# Schematic-1.net
KiCad netlist of a schematic drawn in EAGLE
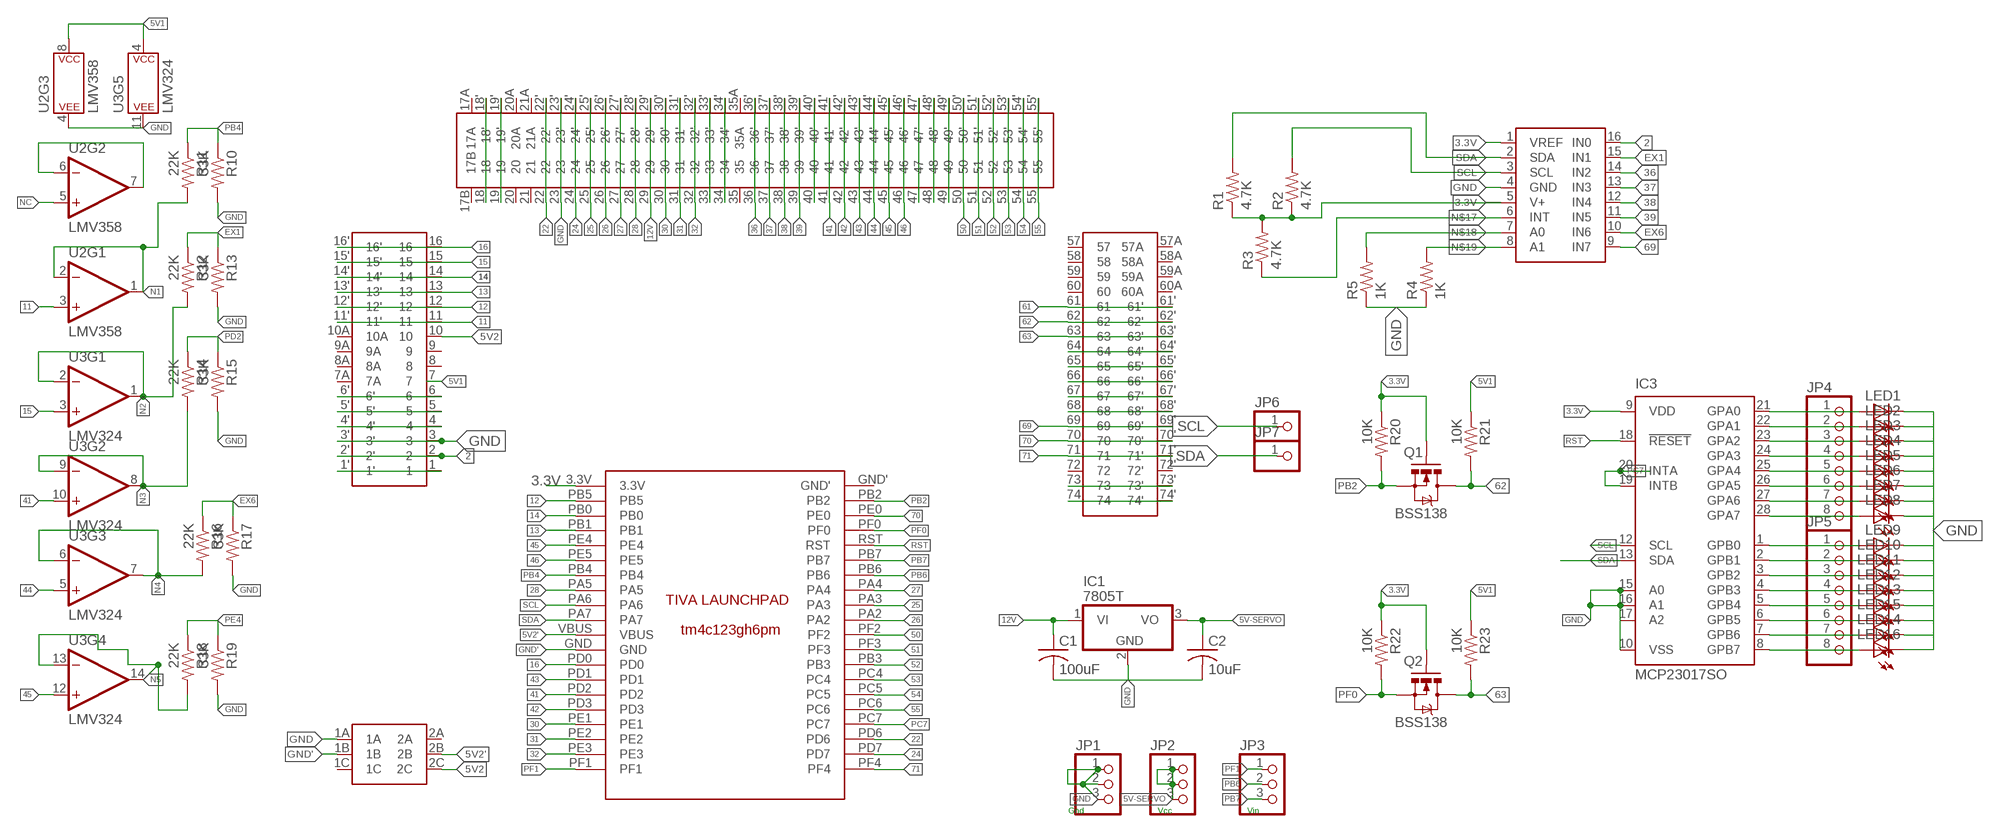
[diagram p0: schematic, sheet 1]

(export (version "E")
  (design (tool "Eeschema 10.0.6"))
  (components
    (comp (ref "C1")
      (value "100uF")
      (footprint "eagle-import:C025-030X050")
      (libsource (lib "eagle-import") (part "C-US025-030X050"))
    )
    (comp (ref "C2")
      (value "10uF")
      (footprint "eagle-import:C025-030X050")
      (libsource (lib "eagle-import") (part "C-US025-030X050"))
    )
    (comp (ref "IC1")
      (value "7805T")
      (footprint "eagle-import:TO220H")
      (libsource (lib "eagle-import") (part "78T05"))
    )
    (comp (ref "IC3")
      (value "MCP23017SO")
      (footprint "eagle-import:SO28W")
      (libsource (lib "eagle-import") (part "MCP23017SO"))
    )
    (comp (ref "JP1")
      (value "PINHD-1X3")
      (footprint "eagle-import:1X03")
      (libsource (lib "eagle-import") (part "PINHD-1X3"))
    )
    (comp (ref "JP2")
      (value "PINHD-1X3")
      (footprint "eagle-import:1X03")
      (libsource (lib "eagle-import") (part "PINHD-1X3"))
    )
    (comp (ref "JP3")
      (value "PINHD-1X3")
      (footprint "eagle-import:1X03")
      (libsource (lib "eagle-import") (part "PINHD-1X3"))
    )
    (comp (ref "JP4")
      (value "PINHD-1X8BIG")
      (footprint "eagle-import:1X08-BIG")
      (libsource (lib "eagle-import") (part "PINHD-1X8BIG"))
    )
    (comp (ref "JP5")
      (value "PINHD-1X8BIG")
      (footprint "eagle-import:1X08-BIG")
      (libsource (lib "eagle-import") (part "PINHD-1X8BIG"))
    )
    (comp (ref "JP6")
      (value "PINHD-1X1")
      (footprint "eagle-import:1X01")
      (libsource (lib "eagle-import") (part "PINHD-1X1"))
    )
    (comp (ref "JP7")
      (value "PINHD-1X1")
      (footprint "eagle-import:1X01")
      (libsource (lib "eagle-import") (part "PINHD-1X1"))
    )
    (comp (ref "LED1")
      (value "LEDSMT1206")
      (footprint "eagle-import:1206")
      (libsource (lib "eagle-import") (part "LEDSMT1206"))
    )
    (comp (ref "LED2")
      (value "LEDSMT1206")
      (footprint "eagle-import:1206")
      (libsource (lib "eagle-import") (part "LEDSMT1206"))
    )
    (comp (ref "LED3")
      (value "LEDSMT1206")
      (footprint "eagle-import:1206")
      (libsource (lib "eagle-import") (part "LEDSMT1206"))
    )
    (comp (ref "LED4")
      (value "LEDSMT1206")
      (footprint "eagle-import:1206")
      (libsource (lib "eagle-import") (part "LEDSMT1206"))
    )
    (comp (ref "LED5")
      (value "LEDSMT1206")
      (footprint "eagle-import:1206")
      (libsource (lib "eagle-import") (part "LEDSMT1206"))
    )
    (comp (ref "LED6")
      (value "LEDSMT1206")
      (footprint "eagle-import:1206")
      (libsource (lib "eagle-import") (part "LEDSMT1206"))
    )
    (comp (ref "LED7")
      (value "LEDSMT1206")
      (footprint "eagle-import:1206")
      (libsource (lib "eagle-import") (part "LEDSMT1206"))
    )
    (comp (ref "LED8")
      (value "LEDSMT1206")
      (footprint "eagle-import:1206")
      (libsource (lib "eagle-import") (part "LEDSMT1206"))
    )
    (comp (ref "LED9")
      (value "LEDSMT1206")
      (footprint "eagle-import:1206")
      (libsource (lib "eagle-import") (part "LEDSMT1206"))
    )
    (comp (ref "LED10")
      (value "LEDSMT1206")
      (footprint "eagle-import:1206")
      (libsource (lib "eagle-import") (part "LEDSMT1206"))
    )
    (comp (ref "LED11")
      (value "LEDSMT1206")
      (footprint "eagle-import:1206")
      (libsource (lib "eagle-import") (part "LEDSMT1206"))
    )
    (comp (ref "LED12")
      (value "LEDSMT1206")
      (footprint "eagle-import:1206")
      (libsource (lib "eagle-import") (part "LEDSMT1206"))
    )
    (comp (ref "LED13")
      (value "LEDSMT1206")
      (footprint "eagle-import:1206")
      (libsource (lib "eagle-import") (part "LEDSMT1206"))
    )
    (comp (ref "LED14")
      (value "LEDSMT1206")
      (footprint "eagle-import:1206")
      (libsource (lib "eagle-import") (part "LEDSMT1206"))
    )
    (comp (ref "LED15")
      (value "LEDSMT1206")
      (footprint "eagle-import:1206")
      (libsource (lib "eagle-import") (part "LEDSMT1206"))
    )
    (comp (ref "LED16")
      (value "LEDSMT1206")
      (footprint "eagle-import:1206")
      (libsource (lib "eagle-import") (part "LEDSMT1206"))
    )
    (comp (ref "Q1")
      (value "BSS138")
      (footprint "eagle-import:SOT23-3")
      (libsource (lib "eagle-import") (part "MOSFET-NCHANNELSMD"))
    )
    (comp (ref "Q2")
      (value "BSS138")
      (footprint "eagle-import:SOT23-3")
      (libsource (lib "eagle-import") (part "MOSFET-NCHANNELSMD"))
    )
    (comp (ref "R1")
      (value "4.7K")
      (footprint "eagle-import:M1206")
      (libsource (lib "eagle-import") (part "rcl_R-US_M1206"))
    )
    (comp (ref "R2")
      (value "4.7K")
      (footprint "eagle-import:M1206")
      (libsource (lib "eagle-import") (part "rcl_R-US_M1206"))
    )
    (comp (ref "R3")
      (value "4.7K")
      (footprint "eagle-import:M1206")
      (libsource (lib "eagle-import") (part "rcl_R-US_M1206"))
    )
    (comp (ref "R4")
      (value "1K")
      (footprint "eagle-import:M1206")
      (libsource (lib "eagle-import") (part "rcl_R-US_M1206"))
    )
    (comp (ref "R5")
      (value "1K")
      (footprint "eagle-import:M1206")
      (libsource (lib "eagle-import") (part "rcl_R-US_M1206"))
    )
    (comp (ref "R10")
      (value "33K")
      (footprint "eagle-import:M1206")
      (libsource (lib "eagle-import") (part "R-US_M1206"))
    )
    (comp (ref "R11")
      (value "22K")
      (footprint "eagle-import:M1206")
      (libsource (lib "eagle-import") (part "R-US_M1206"))
    )
    (comp (ref "R12")
      (value "22K")
      (footprint "eagle-import:M1206")
      (libsource (lib "eagle-import") (part "R-US_M1206"))
    )
    (comp (ref "R13")
      (value "33K")
      (footprint "eagle-import:M1206")
      (libsource (lib "eagle-import") (part "R-US_M1206"))
    )
    (comp (ref "R14")
      (value "22K")
      (footprint "eagle-import:M1206")
      (libsource (lib "eagle-import") (part "R-US_M1206"))
    )
    (comp (ref "R15")
      (value "33K")
      (footprint "eagle-import:M1206")
      (libsource (lib "eagle-import") (part "R-US_M1206"))
    )
    (comp (ref "R16")
      (value "22K")
      (footprint "eagle-import:M1206")
      (libsource (lib "eagle-import") (part "R-US_M1206"))
    )
    (comp (ref "R17")
      (value "33K")
      (footprint "eagle-import:M1206")
      (libsource (lib "eagle-import") (part "R-US_M1206"))
    )
    (comp (ref "R18")
      (value "22K")
      (footprint "eagle-import:M1206")
      (libsource (lib "eagle-import") (part "R-US_M1206"))
    )
    (comp (ref "R19")
      (value "33K")
      (footprint "eagle-import:M1206")
      (libsource (lib "eagle-import") (part "R-US_M1206"))
    )
    (comp (ref "R20")
      (value "10K")
      (footprint "eagle-import:1206")
      (libsource (lib "eagle-import") (part "RESISTOR1206"))
    )
    (comp (ref "R21")
      (value "10K")
      (footprint "eagle-import:1206")
      (libsource (lib "eagle-import") (part "RESISTOR1206"))
    )
    (comp (ref "R22")
      (value "10K")
      (footprint "eagle-import:1206")
      (libsource (lib "eagle-import") (part "RESISTOR1206"))
    )
    (comp (ref "R23")
      (value "10K")
      (footprint "eagle-import:1206")
      (libsource (lib "eagle-import") (part "RESISTOR1206"))
    )
    (comp (ref "U$1")
      (value "DAUGHTERBOARDDAUGHTERBOARD")
      (footprint "eagle-import:DAUGHTERBOARD")
      (libsource (lib "eagle-import") (part "DAUGHTERBOARDDAUGHTERBOARD"))
    )
    (comp (ref "U$2")
      (value "TIVA_LAUNCHPADTIVA_LAUNCHPAD")
      (footprint "eagle-import:TIVA_LAUNCHPAD")
      (libsource (lib "eagle-import") (part "TIVA_LAUNCHPADTIVA_LAUNCHPAD"))
    )
    (comp (ref "U$3")
      (value "SELF-LOCKING_SWITCHSELF-LOCKING_SWITCH")
      (footprint "eagle-import:SELF-LOCKING_SWITCH")
      (libsource (lib "eagle-import") (part "SELF-LOCKING_SWITCHSELF-LOCKING_SWITCH"))
    )
    (comp (ref "U$4")
      (value "ADC128D818")
      (footprint "eagle-import:ADC12_SD")
      (libsource (lib "eagle-import") (part "ADC128D818"))
    )
    (comp (ref "U2")
      (value "LMV358")
      (footprint "eagle-import:SO08")
      (libsource (lib "eagle-import") (part "LMV358SOIC"))
    )
    (comp (ref "U3")
      (value "LMV324")
      (footprint "eagle-import:SO14")
      (libsource (lib "eagle-import") (part "LMV324"))
    )
  )
  (nets
    (net (code "1") (name "2") (class "Default")
      (node (ref "U$1") (pin "2") (pinfunction "2_2") (pintype "output"))
      (node (ref "U$1") (pin "2'") (pinfunction "2'_2'") (pintype "output"))
      (node (ref "U$4") (pin "16") (pinfunction "IN0_16") (pintype "bidirectional"))
    )
    (net (code "2") (name "3.3V") (class "Default")
      (node (ref "IC3") (pin "9") (pinfunction "VDD_9") (pintype "power_in"))
      (node (ref "Q1") (pin "1") (pinfunction "G_1") (pintype "passive"))
      (node (ref "Q2") (pin "1") (pinfunction "G_1") (pintype "passive"))
      (node (ref "R1") (pin "1") (pinfunction "1_1") (pintype "passive"))
      (node (ref "R2") (pin "1") (pinfunction "1_1") (pintype "passive"))
      (node (ref "R20") (pin "1") (pinfunction "1_1") (pintype "passive"))
      (node (ref "R22") (pin "1") (pinfunction "1_1") (pintype "passive"))
      (node (ref "R3") (pin "2") (pinfunction "2_2") (pintype "passive"))
      (node (ref "U$2") (pin "3.3V") (pinfunction "3.3V_3.3V") (pintype "bidirectional"))
      (node (ref "U$4") (pin "1") (pinfunction "VREF_1") (pintype "bidirectional"))
      (node (ref "U$4") (pin "5") (pinfunction "V+_5") (pintype "bidirectional"))
    )
    (net (code "3") (name "5V-SERVO") (class "Default")
      (node (ref "C2") (pin "1") (pinfunction "1_1") (pintype "passive"))
      (node (ref "IC1") (pin "3") (pinfunction "VO_3") (pintype "passive"))
      (node (ref "JP2") (pin "1") (pinfunction "1_1") (pintype "passive"))
      (node (ref "JP2") (pin "2") (pinfunction "2_2") (pintype "passive"))
      (node (ref "JP2") (pin "3") (pinfunction "3_3") (pintype "passive"))
    )
    (net (code "4") (name "5V1") (class "Default")
      (node (ref "R21") (pin "1") (pinfunction "1_1") (pintype "passive"))
      (node (ref "R23") (pin "1") (pinfunction "1_1") (pintype "passive"))
      (node (ref "U$1") (pin "7") (pinfunction "7_7") (pintype "output"))
      (node (ref "U2") (pin "8") (pinfunction "P$V+_8") (pintype "bidirectional"))
      (node (ref "U3") (pin "4") (pinfunction "P$V+_4") (pintype "bidirectional"))
    )
    (net (code "5") (name "5V2") (class "Default")
      (node (ref "U$1") (pin "10") (pinfunction "10_10") (pintype "output"))
      (node (ref "U$3") (pin "2C") (pinfunction "2C_2C") (pintype "bidirectional"))
    )
    (net (code "6") (name "5V2'") (class "Default")
      (node (ref "U$2") (pin "VBUS") (pinfunction "VBUS_VBUS") (pintype "bidirectional"))
      (node (ref "U$3") (pin "2B") (pinfunction "2B_2B") (pintype "bidirectional"))
    )
    (net (code "7") (name "11") (class "Default")
      (node (ref "U$1") (pin "11") (pinfunction "11_11") (pintype "output"))
      (node (ref "U$1") (pin "11'") (pinfunction "11'_11'") (pintype "output"))
      (node (ref "U2") (pin "3") (pinfunction "+IN_3") (pintype "input"))
    )
    (net (code "8") (name "12") (class "Default")
      (node (ref "U$1") (pin "12") (pinfunction "12_12") (pintype "output"))
      (node (ref "U$1") (pin "12'") (pinfunction "12'_12'") (pintype "output"))
      (node (ref "U$2") (pin "PB5") (pinfunction "PB5_PB5") (pintype "bidirectional"))
    )
    (net (code "9") (name "12V") (class "Default")
      (node (ref "C1") (pin "1") (pinfunction "1_1") (pintype "passive"))
      (node (ref "IC1") (pin "1") (pinfunction "VI_1") (pintype "input"))
      (node (ref "U$1") (pin "29") (pinfunction "29_29") (pintype "output"))
      (node (ref "U$1") (pin "29'") (pinfunction "29'_29'") (pintype "output"))
    )
    (net (code "10") (name "13") (class "Default")
      (node (ref "U$1") (pin "13") (pinfunction "13_13") (pintype "output"))
      (node (ref "U$1") (pin "13'") (pinfunction "13'_13'") (pintype "output"))
      (node (ref "U$2") (pin "PB1") (pinfunction "PB1_PB1") (pintype "bidirectional"))
    )
    (net (code "11") (name "14") (class "Default")
      (node (ref "U$1") (pin "14") (pinfunction "14_14") (pintype "output"))
      (node (ref "U$1") (pin "14'") (pinfunction "14'_14'") (pintype "output"))
      (node (ref "U$2") (pin "PB0") (pinfunction "PB0_PB0") (pintype "bidirectional"))
    )
    (net (code "12") (name "15") (class "Default")
      (node (ref "U$1") (pin "15") (pinfunction "15_15") (pintype "output"))
      (node (ref "U$1") (pin "15'") (pinfunction "15'_15'") (pintype "output"))
      (node (ref "U3") (pin "3") (pinfunction "+IN_3") (pintype "input"))
    )
    (net (code "13") (name "16") (class "Default")
      (node (ref "U$1") (pin "16") (pinfunction "16_16") (pintype "output"))
      (node (ref "U$1") (pin "16'") (pinfunction "16'_16'") (pintype "output"))
      (node (ref "U$2") (pin "PD0") (pinfunction "PD0_PD0") (pintype "bidirectional"))
    )
    (net (code "14") (name "22") (class "Default")
      (node (ref "U$1") (pin "22") (pinfunction "22_22") (pintype "output"))
      (node (ref "U$1") (pin "22'") (pinfunction "22'_22'") (pintype "output"))
      (node (ref "U$2") (pin "PD6") (pinfunction "PD6_PD6") (pintype "bidirectional"))
    )
    (net (code "15") (name "24") (class "Default")
      (node (ref "U$1") (pin "24") (pinfunction "24_24") (pintype "output"))
      (node (ref "U$1") (pin "24'") (pinfunction "24'_24'") (pintype "output"))
      (node (ref "U$2") (pin "PD7") (pinfunction "PD7_PD7") (pintype "bidirectional"))
    )
    (net (code "16") (name "25") (class "Default")
      (node (ref "U$1") (pin "25") (pinfunction "25_25") (pintype "output"))
      (node (ref "U$1") (pin "25'") (pinfunction "25'_25'") (pintype "output"))
      (node (ref "U$2") (pin "PA3") (pinfunction "PA3_PA3") (pintype "bidirectional"))
    )
    (net (code "17") (name "26") (class "Default")
      (node (ref "U$1") (pin "26") (pinfunction "26_26") (pintype "output"))
      (node (ref "U$1") (pin "26'") (pinfunction "26'_26'") (pintype "output"))
      (node (ref "U$2") (pin "PA2") (pinfunction "PA2_PA2") (pintype "bidirectional"))
    )
    (net (code "18") (name "27") (class "Default")
      (node (ref "U$1") (pin "27") (pinfunction "27_27") (pintype "output"))
      (node (ref "U$1") (pin "27'") (pinfunction "27'_27'") (pintype "output"))
      (node (ref "U$2") (pin "PA4") (pinfunction "PA4_PA4") (pintype "bidirectional"))
    )
    (net (code "19") (name "28") (class "Default")
      (node (ref "U$1") (pin "28") (pinfunction "28_28") (pintype "output"))
      (node (ref "U$1") (pin "28'") (pinfunction "28'_28'") (pintype "output"))
      (node (ref "U$2") (pin "PA5") (pinfunction "PA5_PA5") (pintype "bidirectional"))
    )
    (net (code "20") (name "30") (class "Default")
      (node (ref "U$1") (pin "30") (pinfunction "30_30") (pintype "output"))
      (node (ref "U$1") (pin "30'") (pinfunction "30'_30'") (pintype "output"))
      (node (ref "U$2") (pin "PE1") (pinfunction "PE1_PE1") (pintype "bidirectional"))
    )
    (net (code "21") (name "31") (class "Default")
      (node (ref "U$1") (pin "31") (pinfunction "31_31") (pintype "output"))
      (node (ref "U$1") (pin "31'") (pinfunction "31'_31'") (pintype "output"))
      (node (ref "U$2") (pin "PE2") (pinfunction "PE2_PE2") (pintype "bidirectional"))
    )
    (net (code "22") (name "32") (class "Default")
      (node (ref "U$1") (pin "32") (pinfunction "32_32") (pintype "output"))
      (node (ref "U$1") (pin "32'") (pinfunction "32'_32'") (pintype "output"))
      (node (ref "U$2") (pin "PE3") (pinfunction "PE3_PE3") (pintype "bidirectional"))
    )
    (net (code "23") (name "36") (class "Default")
      (node (ref "U$1") (pin "36") (pinfunction "36_36") (pintype "output"))
      (node (ref "U$1") (pin "36'") (pinfunction "36'_36'") (pintype "output"))
      (node (ref "U$4") (pin "14") (pinfunction "IN2_14") (pintype "bidirectional"))
    )
    (net (code "24") (name "37") (class "Default")
      (node (ref "U$1") (pin "37") (pinfunction "37_37") (pintype "output"))
      (node (ref "U$1") (pin "37'") (pinfunction "37'_37'") (pintype "output"))
      (node (ref "U$4") (pin "13") (pinfunction "IN3_13") (pintype "bidirectional"))
    )
    (net (code "25") (name "38") (class "Default")
      (node (ref "U$1") (pin "38") (pinfunction "38_38") (pintype "output"))
      (node (ref "U$1") (pin "38'") (pinfunction "38'_38'") (pintype "output"))
      (node (ref "U$4") (pin "12") (pinfunction "IN4_12") (pintype "bidirectional"))
    )
    (net (code "26") (name "39") (class "Default")
      (node (ref "U$1") (pin "39") (pinfunction "39_39") (pintype "output"))
      (node (ref "U$1") (pin "39'") (pinfunction "39'_39'") (pintype "output"))
      (node (ref "U$4") (pin "11") (pinfunction "IN5_11") (pintype "bidirectional"))
    )
    (net (code "27") (name "41") (class "Default")
      (node (ref "U$1") (pin "41") (pinfunction "41_41") (pintype "output"))
      (node (ref "U$1") (pin "41'") (pinfunction "41'_41'") (pintype "output"))
      (node (ref "U$2") (pin "PD2") (pinfunction "PD2_PD2") (pintype "bidirectional"))
      (node (ref "U3") (pin "10") (pinfunction "+IN_10") (pintype "input"))
    )
    (net (code "28") (name "42") (class "Default")
      (node (ref "U$1") (pin "42") (pinfunction "42_42") (pintype "output"))
      (node (ref "U$1") (pin "42'") (pinfunction "42'_42'") (pintype "output"))
      (node (ref "U$2") (pin "PD3") (pinfunction "PD3_PD3") (pintype "bidirectional"))
    )
    (net (code "29") (name "43") (class "Default")
      (node (ref "U$1") (pin "43") (pinfunction "43_43") (pintype "output"))
      (node (ref "U$1") (pin "43'") (pinfunction "43'_43'") (pintype "output"))
      (node (ref "U$2") (pin "PD1") (pinfunction "PD1_PD1") (pintype "bidirectional"))
    )
    (net (code "30") (name "44") (class "Default")
      (node (ref "U$1") (pin "44") (pinfunction "44_44") (pintype "output"))
      (node (ref "U$1") (pin "44'") (pinfunction "44'_44'") (pintype "output"))
      (node (ref "U3") (pin "5") (pinfunction "+IN_5") (pintype "input"))
    )
    (net (code "31") (name "45") (class "Default")
      (node (ref "U$1") (pin "45") (pinfunction "45_45") (pintype "output"))
      (node (ref "U$1") (pin "45'") (pinfunction "45'_45'") (pintype "output"))
      (node (ref "U$2") (pin "PE4") (pinfunction "PE4_PE4") (pintype "bidirectional"))
      (node (ref "U3") (pin "12") (pinfunction "+IN_12") (pintype "input"))
    )
    (net (code "32") (name "46") (class "Default")
      (node (ref "U$1") (pin "46") (pinfunction "46_46") (pintype "output"))
      (node (ref "U$1") (pin "46'") (pinfunction "46'_46'") (pintype "output"))
      (node (ref "U$2") (pin "PE5") (pinfunction "PE5_PE5") (pintype "bidirectional"))
    )
    (net (code "33") (name "50") (class "Default")
      (node (ref "U$1") (pin "50") (pinfunction "50_50") (pintype "output"))
      (node (ref "U$1") (pin "50'") (pinfunction "50'_50'") (pintype "output"))
      (node (ref "U$2") (pin "PF2") (pinfunction "PF2_PF2") (pintype "bidirectional"))
    )
    (net (code "34") (name "51") (class "Default")
      (node (ref "U$1") (pin "51") (pinfunction "51_51") (pintype "output"))
      (node (ref "U$1") (pin "51'") (pinfunction "51'_51'") (pintype "output"))
      (node (ref "U$2") (pin "PF3") (pinfunction "PF3_PF3") (pintype "bidirectional"))
    )
    (net (code "35") (name "52") (class "Default")
      (node (ref "U$1") (pin "52") (pinfunction "52_52") (pintype "output"))
      (node (ref "U$1") (pin "52'") (pinfunction "52'_52'") (pintype "output"))
      (node (ref "U$2") (pin "PB3") (pinfunction "PB3_PB3") (pintype "bidirectional"))
    )
    (net (code "36") (name "53") (class "Default")
      (node (ref "U$1") (pin "53") (pinfunction "53_53") (pintype "output"))
      (node (ref "U$1") (pin "53'") (pinfunction "53'_53'") (pintype "output"))
      (node (ref "U$2") (pin "PC4") (pinfunction "PC4_PC4") (pintype "bidirectional"))
    )
    (net (code "37") (name "54") (class "Default")
      (node (ref "U$1") (pin "54") (pinfunction "54_54") (pintype "output"))
      (node (ref "U$1") (pin "54'") (pinfunction "54'_54'") (pintype "output"))
      (node (ref "U$2") (pin "PC5") (pinfunction "PC5_PC5") (pintype "bidirectional"))
    )
    (net (code "38") (name "55") (class "Default")
      (node (ref "U$1") (pin "55") (pinfunction "55_55") (pintype "output"))
      (node (ref "U$1") (pin "55'") (pinfunction "55'_55'") (pintype "output"))
      (node (ref "U$2") (pin "PC6") (pinfunction "PC6_PC6") (pintype "bidirectional"))
    )
    (net (code "39") (name "61") (class "Default")
      (node (ref "U$1") (pin "61") (pinfunction "61_61") (pintype "output"))
      (node (ref "U$1") (pin "61'") (pinfunction "61'_61'") (pintype "output"))
    )
    (net (code "40") (name "62") (class "Default")
      (node (ref "Q1") (pin "3") (pinfunction "D_3") (pintype "passive"))
      (node (ref "R21") (pin "2") (pinfunction "2_2") (pintype "passive"))
      (node (ref "U$1") (pin "62") (pinfunction "62_62") (pintype "output"))
      (node (ref "U$1") (pin "62'") (pinfunction "62'_62'") (pintype "output"))
    )
    (net (code "41") (name "63") (class "Default")
      (node (ref "Q2") (pin "3") (pinfunction "D_3") (pintype "passive"))
      (node (ref "R23") (pin "2") (pinfunction "2_2") (pintype "passive"))
      (node (ref "U$1") (pin "63") (pinfunction "63_63") (pintype "output"))
      (node (ref "U$1") (pin "63'") (pinfunction "63'_63'") (pintype "output"))
    )
    (net (code "42") (name "69") (class "Default")
      (node (ref "U$1") (pin "69") (pinfunction "69_69") (pintype "output"))
      (node (ref "U$1") (pin "69'") (pinfunction "69'_69'") (pintype "output"))
      (node (ref "U$4") (pin "9") (pinfunction "IN7_9") (pintype "bidirectional"))
    )
    (net (code "43") (name "70") (class "Default")
      (node (ref "U$1") (pin "70") (pinfunction "70_70") (pintype "output"))
      (node (ref "U$1") (pin "70'") (pinfunction "70'_70'") (pintype "output"))
      (node (ref "U$2") (pin "PE0") (pinfunction "PE0_PE0") (pintype "bidirectional"))
    )
    (net (code "44") (name "71") (class "Default")
      (node (ref "U$1") (pin "71") (pinfunction "71_71") (pintype "output"))
      (node (ref "U$1") (pin "71'") (pinfunction "71'_71'") (pintype "output"))
      (node (ref "U$2") (pin "PF4") (pinfunction "PF4_PF4") (pintype "bidirectional"))
    )
    (net (code "45") (name "EX1") (class "Default")
      (node (ref "R12") (pin "1") (pinfunction "1_1") (pintype "passive"))
      (node (ref "R13") (pin "1") (pinfunction "1_1") (pintype "passive"))
      (node (ref "U$4") (pin "15") (pinfunction "IN1_15") (pintype "bidirectional"))
    )
    (net (code "46") (name "EX6") (class "Default")
      (node (ref "R16") (pin "1") (pinfunction "1_1") (pintype "passive"))
      (node (ref "R17") (pin "1") (pinfunction "1_1") (pintype "passive"))
      (node (ref "U$4") (pin "10") (pinfunction "IN6_10") (pintype "bidirectional"))
    )
    (net (code "47") (name "GND") (class "Default")
      (node (ref "C1") (pin "2") (pinfunction "2_2") (pintype "passive"))
      (node (ref "C2") (pin "2") (pinfunction "2_2") (pintype "passive"))
      (node (ref "IC1") (pin "2") (pinfunction "GND_2") (pintype "passive"))
      (node (ref "IC3") (pin "10") (pinfunction "VSS_10") (pintype "power_in"))
      (node (ref "IC3") (pin "15") (pinfunction "A0_15") (pintype "input"))
      (node (ref "IC3") (pin "16") (pinfunction "A1_16") (pintype "input"))
      (node (ref "IC3") (pin "17") (pinfunction "A2_17") (pintype "input"))
      (node (ref "JP1") (pin "1") (pinfunction "1_1") (pintype "passive"))
      (node (ref "JP1") (pin "2") (pinfunction "2_2") (pintype "passive"))
      (node (ref "JP1") (pin "3") (pinfunction "3_3") (pintype "passive"))
      (node (ref "LED1") (pin "C") (pinfunction "C_C") (pintype "passive"))
      (node (ref "LED10") (pin "C") (pinfunction "C_C") (pintype "passive"))
      (node (ref "LED11") (pin "C") (pinfunction "C_C") (pintype "passive"))
      (node (ref "LED12") (pin "C") (pinfunction "C_C") (pintype "passive"))
      (node (ref "LED13") (pin "C") (pinfunction "C_C") (pintype "passive"))
      (node (ref "LED14") (pin "C") (pinfunction "C_C") (pintype "passive"))
      (node (ref "LED15") (pin "C") (pinfunction "C_C") (pintype "passive"))
      (node (ref "LED16") (pin "C") (pinfunction "C_C") (pintype "passive"))
      (node (ref "LED2") (pin "C") (pinfunction "C_C") (pintype "passive"))
      (node (ref "LED3") (pin "C") (pinfunction "C_C") (pintype "passive"))
      (node (ref "LED4") (pin "C") (pinfunction "C_C") (pintype "passive"))
      (node (ref "LED5") (pin "C") (pinfunction "C_C") (pintype "passive"))
      (node (ref "LED6") (pin "C") (pinfunction "C_C") (pintype "passive"))
      (node (ref "LED7") (pin "C") (pinfunction "C_C") (pintype "passive"))
      (node (ref "LED8") (pin "C") (pinfunction "C_C") (pintype "passive"))
      (node (ref "LED9") (pin "C") (pinfunction "C_C") (pintype "passive"))
      (node (ref "R10") (pin "2") (pinfunction "2_2") (pintype "passive"))
      (node (ref "R13") (pin "2") (pinfunction "2_2") (pintype "passive"))
      (node (ref "R15") (pin "2") (pinfunction "2_2") (pintype "passive"))
      (node (ref "R17") (pin "2") (pinfunction "2_2") (pintype "passive"))
      (node (ref "R19") (pin "2") (pinfunction "2_2") (pintype "passive"))
      (node (ref "R4") (pin "1") (pinfunction "1_1") (pintype "passive"))
      (node (ref "R5") (pin "1") (pinfunction "1_1") (pintype "passive"))
      (node (ref "U$1") (pin "23") (pinfunction "23_23") (pintype "output"))
      (node (ref "U$1") (pin "23'") (pinfunction "23'_23'") (pintype "output"))
      (node (ref "U$1") (pin "3") (pinfunction "3_3") (pintype "output"))
      (node (ref "U$1") (pin "3'") (pinfunction "3'_3'") (pintype "output"))
      (node (ref "U$3") (pin "1A") (pinfunction "1A_1A") (pintype "bidirectional"))
      (node (ref "U$4") (pin "4") (pinfunction "GND_4") (pintype "bidirectional"))
      (node (ref "U2") (pin "4") (pinfunction "P$V-_4") (pintype "bidirectional"))
      (node (ref "U3") (pin "11") (pinfunction "P$V-_11") (pintype "bidirectional"))
    )
    (net (code "48") (name "GND'") (class "Default")
      (node (ref "U$2") (pin "GND") (pinfunction "GND_GND") (pintype "bidirectional"))
      (node (ref "U$3") (pin "1B") (pinfunction "1B_1B") (pintype "bidirectional"))
    )
    (net (code "49") (name "N$17") (class "Default")
      (node (ref "R3") (pin "1") (pinfunction "1_1") (pintype "passive"))
      (node (ref "U$4") (pin "6") (pinfunction "INT_6") (pintype "bidirectional"))
    )
    (net (code "50") (name "N$18") (class "Default")
      (node (ref "R5") (pin "2") (pinfunction "2_2") (pintype "passive"))
      (node (ref "U$4") (pin "7") (pinfunction "A0_7") (pintype "bidirectional"))
    )
    (net (code "51") (name "N$19") (class "Default")
      (node (ref "R4") (pin "2") (pinfunction "2_2") (pintype "passive"))
      (node (ref "U$4") (pin "8") (pinfunction "A1_8") (pintype "bidirectional"))
    )
    (net (code "52") (name "N1") (class "Default")
      (node (ref "R11") (pin "2") (pinfunction "2_2") (pintype "passive"))
      (node (ref "U2") (pin "1") (pinfunction "OUT_1") (pintype "output"))
      (node (ref "U2") (pin "2") (pinfunction "-IN_2") (pintype "input"))
    )
    (net (code "53") (name "N2") (class "Default")
      (node (ref "R12") (pin "2") (pinfunction "2_2") (pintype "passive"))
      (node (ref "U3") (pin "1") (pinfunction "OUT_1") (pintype "output"))
      (node (ref "U3") (pin "2") (pinfunction "-IN_2") (pintype "input"))
    )
    (net (code "54") (name "N3") (class "Default")
      (node (ref "R14") (pin "2") (pinfunction "2_2") (pintype "passive"))
      (node (ref "U3") (pin "8") (pinfunction "OUT_8") (pintype "output"))
      (node (ref "U3") (pin "9") (pinfunction "-IN_9") (pintype "input"))
    )
    (net (code "55") (name "N4") (class "Default")
      (node (ref "R16") (pin "2") (pinfunction "2_2") (pintype "passive"))
      (node (ref "U3") (pin "6") (pinfunction "-IN_6") (pintype "input"))
      (node (ref "U3") (pin "7") (pinfunction "OUT_7") (pintype "output"))
    )
    (net (code "56") (name "N5") (class "Default")
      (node (ref "R18") (pin "2") (pinfunction "2_2") (pintype "passive"))
      (node (ref "U3") (pin "13") (pinfunction "-IN_13") (pintype "input"))
      (node (ref "U3") (pin "14") (pinfunction "OUT_14") (pintype "output"))
    )
    (net (code "57") (name "NC") (class "Default")
      (node (ref "U2") (pin "5") (pinfunction "+IN_5") (pintype "input"))
    )
    (net (code "58") (name "Net-(IC3-GPA0)") (class "Default")
      (node (ref "IC3") (pin "21") (pinfunction "GPA0_21") (pintype "bidirectional"))
      (node (ref "JP4") (pin "1") (pinfunction "1_1") (pintype "passive"))
      (node (ref "LED1") (pin "A") (pinfunction "A_A") (pintype "passive"))
    )
    (net (code "59") (name "Net-(IC3-GPA1)") (class "Default")
      (node (ref "IC3") (pin "22") (pinfunction "GPA1_22") (pintype "bidirectional"))
      (node (ref "JP4") (pin "2") (pinfunction "2_2") (pintype "passive"))
      (node (ref "LED2") (pin "A") (pinfunction "A_A") (pintype "passive"))
    )
    (net (code "60") (name "Net-(IC3-GPA2)") (class "Default")
      (node (ref "IC3") (pin "23") (pinfunction "GPA2_23") (pintype "bidirectional"))
      (node (ref "JP4") (pin "3") (pinfunction "3_3") (pintype "passive"))
      (node (ref "LED3") (pin "A") (pinfunction "A_A") (pintype "passive"))
    )
    (net (code "61") (name "Net-(IC3-GPA3)") (class "Default")
      (node (ref "IC3") (pin "24") (pinfunction "GPA3_24") (pintype "bidirectional"))
      (node (ref "JP4") (pin "4") (pinfunction "4_4") (pintype "passive"))
      (node (ref "LED4") (pin "A") (pinfunction "A_A") (pintype "passive"))
    )
    (net (code "62") (name "Net-(IC3-GPA4)") (class "Default")
      (node (ref "IC3") (pin "25") (pinfunction "GPA4_25") (pintype "bidirectional"))
      (node (ref "JP4") (pin "5") (pinfunction "5_5") (pintype "passive"))
      (node (ref "LED5") (pin "A") (pinfunction "A_A") (pintype "passive"))
    )
    (net (code "63") (name "Net-(IC3-GPA5)") (class "Default")
      (node (ref "IC3") (pin "26") (pinfunction "GPA5_26") (pintype "bidirectional"))
      (node (ref "JP4") (pin "6") (pinfunction "6_6") (pintype "passive"))
      (node (ref "LED6") (pin "A") (pinfunction "A_A") (pintype "passive"))
    )
    (net (code "64") (name "Net-(IC3-GPA6)") (class "Default")
      (node (ref "IC3") (pin "27") (pinfunction "GPA6_27") (pintype "bidirectional"))
      (node (ref "JP4") (pin "7") (pinfunction "7_7") (pintype "passive"))
      (node (ref "LED7") (pin "A") (pinfunction "A_A") (pintype "passive"))
    )
    (net (code "65") (name "Net-(IC3-GPA7)") (class "Default")
      (node (ref "IC3") (pin "28") (pinfunction "GPA7_28") (pintype "bidirectional"))
      (node (ref "JP4") (pin "8") (pinfunction "8_8") (pintype "passive"))
      (node (ref "LED8") (pin "A") (pinfunction "A_A") (pintype "passive"))
    )
    (net (code "66") (name "Net-(IC3-GPB0)") (class "Default")
      (node (ref "IC3") (pin "1") (pinfunction "GPB0_1") (pintype "bidirectional"))
      (node (ref "JP5") (pin "1") (pinfunction "1_1") (pintype "passive"))
      (node (ref "LED9") (pin "A") (pinfunction "A_A") (pintype "passive"))
    )
    (net (code "67") (name "Net-(IC3-GPB1)") (class "Default")
      (node (ref "IC3") (pin "2") (pinfunction "GPB1_2") (pintype "bidirectional"))
      (node (ref "JP5") (pin "2") (pinfunction "2_2") (pintype "passive"))
      (node (ref "LED10") (pin "A") (pinfunction "A_A") (pintype "passive"))
    )
    (net (code "68") (name "Net-(IC3-GPB2)") (class "Default")
      (node (ref "IC3") (pin "3") (pinfunction "GPB2_3") (pintype "bidirectional"))
      (node (ref "JP5") (pin "3") (pinfunction "3_3") (pintype "passive"))
      (node (ref "LED11") (pin "A") (pinfunction "A_A") (pintype "passive"))
    )
    (net (code "69") (name "Net-(IC3-GPB3)") (class "Default")
      (node (ref "IC3") (pin "4") (pinfunction "GPB3_4") (pintype "bidirectional"))
      (node (ref "JP5") (pin "4") (pinfunction "4_4") (pintype "passive"))
      (node (ref "LED12") (pin "A") (pinfunction "A_A") (pintype "passive"))
    )
    (net (code "70") (name "Net-(IC3-GPB4)") (class "Default")
      (node (ref "IC3") (pin "5") (pinfunction "GPB4_5") (pintype "bidirectional"))
      (node (ref "JP5") (pin "5") (pinfunction "5_5") (pintype "passive"))
      (node (ref "LED13") (pin "A") (pinfunction "A_A") (pintype "passive"))
    )
    (net (code "71") (name "Net-(IC3-GPB5)") (class "Default")
      (node (ref "IC3") (pin "6") (pinfunction "GPB5_6") (pintype "bidirectional"))
      (node (ref "JP5") (pin "6") (pinfunction "6_6") (pintype "passive"))
      (node (ref "LED15") (pin "A") (pinfunction "A_A") (pintype "passive"))
    )
    (net (code "72") (name "Net-(IC3-GPB6)") (class "Default")
      (node (ref "IC3") (pin "7") (pinfunction "GPB6_7") (pintype "bidirectional"))
      (node (ref "JP5") (pin "7") (pinfunction "7_7") (pintype "passive"))
      (node (ref "LED14") (pin "A") (pinfunction "A_A") (pintype "passive"))
    )
    (net (code "73") (name "Net-(IC3-GPB7)") (class "Default")
      (node (ref "IC3") (pin "8") (pinfunction "GPB7_8") (pintype "bidirectional"))
      (node (ref "JP5") (pin "8") (pinfunction "8_8") (pintype "passive"))
      (node (ref "LED16") (pin "A") (pinfunction "A_A") (pintype "passive"))
    )
    (net (code "74") (name "Net-(U$1-Pad1')") (class "Default")
      (node (ref "U$1") (pin "1") (pinfunction "1_1") (pintype "output"))
      (node (ref "U$1") (pin "1'") (pinfunction "1'_1'") (pintype "output"))
    )
    (net (code "75") (name "Net-(U$1-Pad4')") (class "Default")
      (node (ref "U$1") (pin "4") (pinfunction "4_4") (pintype "output"))
      (node (ref "U$1") (pin "4'") (pinfunction "4'_4'") (pintype "output"))
    )
    (net (code "76") (name "Net-(U$1-Pad5')") (class "Default")
      (node (ref "U$1") (pin "5") (pinfunction "5_5") (pintype "output"))
      (node (ref "U$1") (pin "5'") (pinfunction "5'_5'") (pintype "output"))
    )
    (net (code "77") (name "Net-(U$1-Pad6')") (class "Default")
      (node (ref "U$1") (pin "6") (pinfunction "6_6") (pintype "output"))
      (node (ref "U$1") (pin "6'") (pinfunction "6'_6'") (pintype "output"))
    )
    (net (code "78") (name "Net-(U$1-Pad18')") (class "Default")
      (node (ref "U$1") (pin "18") (pinfunction "18_18") (pintype "output"))
      (node (ref "U$1") (pin "18'") (pinfunction "18'_18'") (pintype "output"))
    )
    (net (code "79") (name "Net-(U$1-Pad19')") (class "Default")
      (node (ref "U$1") (pin "19") (pinfunction "19_19") (pintype "output"))
      (node (ref "U$1") (pin "19'") (pinfunction "19'_19'") (pintype "output"))
    )
    (net (code "80") (name "Net-(U$1-Pad33')") (class "Default")
      (node (ref "U$1") (pin "33") (pinfunction "33_33") (pintype "output"))
      (node (ref "U$1") (pin "33'") (pinfunction "33'_33'") (pintype "output"))
    )
    (net (code "81") (name "Net-(U$1-Pad34')") (class "Default")
      (node (ref "U$1") (pin "34") (pinfunction "34_34") (pintype "output"))
      (node (ref "U$1") (pin "34'") (pinfunction "34'_34'") (pintype "output"))
    )
    (net (code "82") (name "Net-(U$1-Pad40')") (class "Default")
      (node (ref "U$1") (pin "40") (pinfunction "40_40") (pintype "output"))
      (node (ref "U$1") (pin "40'") (pinfunction "40'_40'") (pintype "output"))
    )
    (net (code "83") (name "Net-(U$1-Pad47')") (class "Default")
      (node (ref "U$1") (pin "47") (pinfunction "47_47") (pintype "output"))
      (node (ref "U$1") (pin "47'") (pinfunction "47'_47'") (pintype "output"))
    )
    (net (code "84") (name "Net-(U$1-Pad48')") (class "Default")
      (node (ref "U$1") (pin "48") (pinfunction "48_48") (pintype "output"))
      (node (ref "U$1") (pin "48'") (pinfunction "48'_48'") (pintype "output"))
    )
    (net (code "85") (name "Net-(U$1-Pad49')") (class "Default")
      (node (ref "U$1") (pin "49") (pinfunction "49_49") (pintype "output"))
      (node (ref "U$1") (pin "49'") (pinfunction "49'_49'") (pintype "output"))
    )
    (net (code "86") (name "Net-(U$1-Pad64')") (class "Default")
      (node (ref "U$1") (pin "64") (pinfunction "64_64") (pintype "output"))
      (node (ref "U$1") (pin "64'") (pinfunction "64'_64'") (pintype "output"))
    )
    (net (code "87") (name "Net-(U$1-Pad65')") (class "Default")
      (node (ref "U$1") (pin "65") (pinfunction "65_65") (pintype "output"))
      (node (ref "U$1") (pin "65'") (pinfunction "65'_65'") (pintype "output"))
    )
    (net (code "88") (name "Net-(U$1-Pad66')") (class "Default")
      (node (ref "U$1") (pin "66") (pinfunction "66_66") (pintype "output"))
      (node (ref "U$1") (pin "66'") (pinfunction "66'_66'") (pintype "output"))
    )
    (net (code "89") (name "Net-(U$1-Pad67')") (class "Default")
      (node (ref "U$1") (pin "67") (pinfunction "67_67") (pintype "output"))
      (node (ref "U$1") (pin "67'") (pinfunction "67'_67'") (pintype "output"))
    )
    (net (code "90") (name "Net-(U$1-Pad68')") (class "Default")
      (node (ref "U$1") (pin "68") (pinfunction "68_68") (pintype "output"))
      (node (ref "U$1") (pin "68'") (pinfunction "68'_68'") (pintype "output"))
    )
    (net (code "91") (name "Net-(U$1-Pad73')") (class "Default")
      (node (ref "U$1") (pin "73") (pinfunction "73_73") (pintype "output"))
      (node (ref "U$1") (pin "73'") (pinfunction "73'_73'") (pintype "output"))
    )
    (net (code "92") (name "Net-(U$1-Pad74')") (class "Default")
      (node (ref "U$1") (pin "74") (pinfunction "74_74") (pintype "output"))
      (node (ref "U$1") (pin "74'") (pinfunction "74'_74'") (pintype "output"))
    )
    (net (code "93") (name "Net-(U2B--IN)") (class "Default")
      (node (ref "U2") (pin "6") (pinfunction "-IN_6") (pintype "input"))
      (node (ref "U2") (pin "7") (pinfunction "OUT_7") (pintype "output"))
    )
    (net (code "94") (name "PB2") (class "Default")
      (node (ref "Q1") (pin "2") (pinfunction "S_2") (pintype "passive"))
      (node (ref "R20") (pin "2") (pinfunction "2_2") (pintype "passive"))
      (node (ref "U$2") (pin "PB2") (pinfunction "PB2_PB2") (pintype "bidirectional"))
    )
    (net (code "95") (name "PB4") (class "Default")
      (node (ref "R10") (pin "1") (pinfunction "1_1") (pintype "passive"))
      (node (ref "R11") (pin "1") (pinfunction "1_1") (pintype "passive"))
      (node (ref "U$2") (pin "PB4") (pinfunction "PB4_PB4") (pintype "bidirectional"))
    )
    (net (code "96") (name "PB6") (class "Default")
      (node (ref "JP3") (pin "2") (pinfunction "2_2") (pintype "passive"))
      (node (ref "U$2") (pin "PB6") (pinfunction "PB6_PB6") (pintype "bidirectional"))
    )
    (net (code "97") (name "PB7") (class "Default")
      (node (ref "JP3") (pin "3") (pinfunction "3_3") (pintype "passive"))
      (node (ref "U$2") (pin "PB7") (pinfunction "PB7_PB7") (pintype "bidirectional"))
    )
    (net (code "98") (name "PC7") (class "Default")
      (node (ref "IC3") (pin "19") (pinfunction "INTB_19") (pintype "output"))
      (node (ref "IC3") (pin "20") (pinfunction "INTA_20") (pintype "output"))
      (node (ref "U$2") (pin "PC7") (pinfunction "PC7_PC7") (pintype "bidirectional"))
    )
    (net (code "99") (name "PD2") (class "Default")
      (node (ref "R14") (pin "1") (pinfunction "1_1") (pintype "passive"))
      (node (ref "R15") (pin "1") (pinfunction "1_1") (pintype "passive"))
    )
    (net (code "100") (name "PE4") (class "Default")
      (node (ref "R18") (pin "1") (pinfunction "1_1") (pintype "passive"))
      (node (ref "R19") (pin "1") (pinfunction "1_1") (pintype "passive"))
    )
    (net (code "101") (name "PF0") (class "Default")
      (node (ref "Q2") (pin "2") (pinfunction "S_2") (pintype "passive"))
      (node (ref "R22") (pin "2") (pinfunction "2_2") (pintype "passive"))
      (node (ref "U$2") (pin "PF0") (pinfunction "PF0_PF0") (pintype "bidirectional"))
    )
    (net (code "102") (name "PF1") (class "Default")
      (node (ref "JP3") (pin "1") (pinfunction "1_1") (pintype "passive"))
      (node (ref "U$2") (pin "PF1") (pinfunction "PF1_PF1") (pintype "bidirectional"))
    )
    (net (code "103") (name "RST") (class "Default")
      (node (ref "IC3") (pin "18") (pinfunction "~{RESET}_18") (pintype "input"))
      (node (ref "U$2") (pin "RST") (pinfunction "RST_RST") (pintype "bidirectional"))
    )
    (net (code "104") (name "SCL") (class "Default")
      (node (ref "IC3") (pin "12") (pinfunction "SCL_12") (pintype "input"))
      (node (ref "JP6") (pin "1") (pinfunction "1_1") (pintype "passive"))
      (node (ref "R2") (pin "2") (pinfunction "2_2") (pintype "passive"))
      (node (ref "U$2") (pin "PA6") (pinfunction "PA6_PA6") (pintype "bidirectional"))
      (node (ref "U$4") (pin "3") (pinfunction "SCL_3") (pintype "bidirectional"))
    )
    (net (code "105") (name "SDA") (class "Default")
      (node (ref "IC3") (pin "13") (pinfunction "SDA_13") (pintype "bidirectional"))
      (node (ref "JP7") (pin "1") (pinfunction "1_1") (pintype "passive"))
      (node (ref "R1") (pin "2") (pinfunction "2_2") (pintype "passive"))
      (node (ref "U$2") (pin "PA7") (pinfunction "PA7_PA7") (pintype "bidirectional"))
      (node (ref "U$4") (pin "2") (pinfunction "SDA_2") (pintype "bidirectional"))
    )
    (net (code "106") (name "unconnected-(U$1-Pad7A)") (class "Default")
      (node (ref "U$1") (pin "7A") (pinfunction "7A_7A") (pintype "output"))
    )
    (net (code "107") (name "unconnected-(U$1-Pad8)") (class "Default")
      (node (ref "U$1") (pin "8") (pinfunction "8_8") (pintype "output"))
    )
    (net (code "108") (name "unconnected-(U$1-Pad8A)") (class "Default")
      (node (ref "U$1") (pin "8A") (pinfunction "8A_8A") (pintype "output"))
    )
    (net (code "109") (name "unconnected-(U$1-Pad9)") (class "Default")
      (node (ref "U$1") (pin "9") (pinfunction "9_9") (pintype "output"))
    )
    (net (code "110") (name "unconnected-(U$1-Pad9A)") (class "Default")
      (node (ref "U$1") (pin "9A") (pinfunction "9A_9A") (pintype "output"))
    )
    (net (code "111") (name "unconnected-(U$1-Pad10A)") (class "Default")
      (node (ref "U$1") (pin "10A") (pinfunction "10A_10A") (pintype "output"))
    )
    (net (code "112") (name "unconnected-(U$1-Pad17A)") (class "Default")
      (node (ref "U$1") (pin "17A") (pinfunction "17A_17A") (pintype "output"))
    )
    (net (code "113") (name "unconnected-(U$1-Pad17B)") (class "Default")
      (node (ref "U$1") (pin "17B") (pinfunction "17B_17B") (pintype "output"))
    )
    (net (code "114") (name "unconnected-(U$1-Pad20)") (class "Default")
      (node (ref "U$1") (pin "20") (pinfunction "20_20") (pintype "output"))
    )
    (net (code "115") (name "unconnected-(U$1-Pad20A)") (class "Default")
      (node (ref "U$1") (pin "20A") (pinfunction "20A_20A") (pintype "output"))
    )
    (net (code "116") (name "unconnected-(U$1-Pad21)") (class "Default")
      (node (ref "U$1") (pin "21") (pinfunction "21_21") (pintype "output"))
    )
    (net (code "117") (name "unconnected-(U$1-Pad21A)") (class "Default")
      (node (ref "U$1") (pin "21A") (pinfunction "21A_21A") (pintype "output"))
    )
    (net (code "118") (name "unconnected-(U$1-Pad35)") (class "Default")
      (node (ref "U$1") (pin "35") (pinfunction "35_35") (pintype "output"))
    )
    (net (code "119") (name "unconnected-(U$1-Pad35A)") (class "Default")
      (node (ref "U$1") (pin "35A") (pinfunction "35A_35A") (pintype "output"))
    )
    (net (code "120") (name "unconnected-(U$1-Pad57)") (class "Default")
      (node (ref "U$1") (pin "57") (pinfunction "57_57") (pintype "output"))
    )
    (net (code "121") (name "unconnected-(U$1-Pad57A)") (class "Default")
      (node (ref "U$1") (pin "57A") (pinfunction "57A_57A") (pintype "output"))
    )
    (net (code "122") (name "unconnected-(U$1-Pad58)") (class "Default")
      (node (ref "U$1") (pin "58") (pinfunction "58_58") (pintype "output"))
    )
    (net (code "123") (name "unconnected-(U$1-Pad58A)") (class "Default")
      (node (ref "U$1") (pin "58A") (pinfunction "58A_58A") (pintype "output"))
    )
    (net (code "124") (name "unconnected-(U$1-Pad59)") (class "Default")
      (node (ref "U$1") (pin "59") (pinfunction "59_59") (pintype "output"))
    )
    (net (code "125") (name "unconnected-(U$1-Pad59A)") (class "Default")
      (node (ref "U$1") (pin "59A") (pinfunction "59A_59A") (pintype "output"))
    )
    (net (code "126") (name "unconnected-(U$1-Pad60)") (class "Default")
      (node (ref "U$1") (pin "60") (pinfunction "60_60") (pintype "output"))
    )
    (net (code "127") (name "unconnected-(U$1-Pad60A)") (class "Default")
      (node (ref "U$1") (pin "60A") (pinfunction "60A_60A") (pintype "output"))
    )
    (net (code "128") (name "unconnected-(U$1-Pad72')") (class "Default")
      (node (ref "U$1") (pin "72'") (pinfunction "72'_72'") (pintype "output"))
    )
    (net (code "129") (name "unconnected-(U$1-Pad72)") (class "Default")
      (node (ref "U$1") (pin "72") (pinfunction "72_72") (pintype "output"))
    )
    (net (code "130") (name "unconnected-(U$2-PadGND')") (class "Default")
      (node (ref "U$2") (pin "GND'") (pinfunction "GND'_GND'") (pintype "bidirectional"))
    )
    (net (code "131") (name "unconnected-(U$3-Pad1C)") (class "Default")
      (node (ref "U$3") (pin "1C") (pinfunction "1C_1C") (pintype "bidirectional"))
    )
    (net (code "132") (name "unconnected-(U$3-Pad2A)") (class "Default")
      (node (ref "U$3") (pin "2A") (pinfunction "2A_2A") (pintype "bidirectional"))
    )
  )
)
